# Level_Shifter.net
KiCad netlist of a schematic drawn in Altium Designer
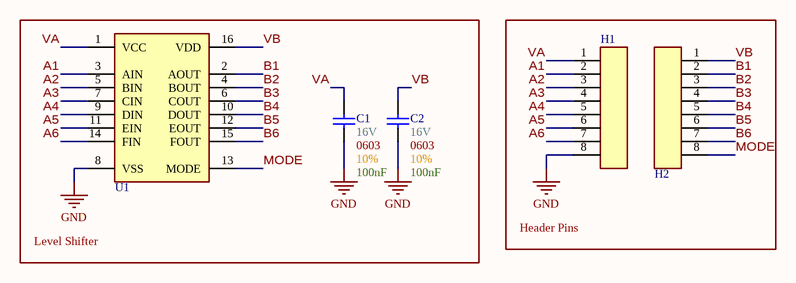
[diagram p0: Level Shifter.SchDoc]

(export (version "E")
  (design (tool "Eeschema 10.0.6"))
  (components
    (comp (ref "C1")
      (value "[Cap] 0603 0.1uF 10% 16V")
      (footprint "[Cap] SMD 0603")
      (description "CC0603KRX7R7BB104")
      (fields
        (field (name "MAX VOLTAGE") "16V")
        (field (name "SIZE PACKAGE") "0603")
        (field (name "TOLERANCE") "10%")
        (field (name "CAPACITANCE") "100nF")
      )
      (libsource (lib "Capacitors") (part "[Cap] 0603 0.1uF 10% 16V"))
    )
    (comp (ref "C2")
      (value "[Cap] 0603 0.1uF 10% 16V")
      (footprint "[Cap] SMD 0603")
      (description "CC0603KRX7R7BB104")
      (fields
        (field (name "MAX VOLTAGE") "16V")
        (field (name "SIZE PACKAGE") "0603")
        (field (name "TOLERANCE") "10%")
        (field (name "CAPACITANCE") "100nF")
      )
      (libsource (lib "Capacitors") (part "[Cap] 0603 0.1uF 10% 16V"))
    )
    (comp (ref "H1")
      (value "1x8 Header")
      (footprint "[Header] 1x8 Male")
      (description "2.54mm pitch")
      (libsource (lib "") (part "[Header] 1x8 Male_1"))
    )
    (comp (ref "H2")
      (value "1x8 Header")
      (footprint "[Header] 1x8 Male")
      (description "2.54mm pitch")
      (libsource (lib "Connectors") (part "[Header] 1x8 Male"))
    )
    (comp (ref "U1")
      (value "[Level Shifter] 3-18V Unidirectional")
      (footprint "[Level Shifter] 3-18V Unidirectional")
      (description "MC14504BDTR2G")
      (libsource (lib "ICs") (part "[Level Shifter] 3-18V Unidirectional"))
    )
  )
  (nets
    (net (code "1") (name "/A1") (class "Default")
      (node (ref "H1") (pin "2") (pinfunction "2_2") (pintype "passive"))
      (node (ref "U1") (pin "3") (pinfunction "AIN_3") (pintype "passive"))
    )
    (net (code "2") (name "/A2") (class "Default")
      (node (ref "H1") (pin "3") (pinfunction "3_3") (pintype "passive"))
      (node (ref "U1") (pin "5") (pinfunction "BIN_5") (pintype "passive"))
    )
    (net (code "3") (name "/A3") (class "Default")
      (node (ref "H1") (pin "4") (pinfunction "4_4") (pintype "passive"))
      (node (ref "U1") (pin "7") (pinfunction "CIN_7") (pintype "passive"))
    )
    (net (code "4") (name "/A4") (class "Default")
      (node (ref "H1") (pin "5") (pinfunction "5_5") (pintype "passive"))
      (node (ref "U1") (pin "9") (pinfunction "DIN_9") (pintype "passive"))
    )
    (net (code "5") (name "/A5") (class "Default")
      (node (ref "H1") (pin "6") (pinfunction "6_6") (pintype "passive"))
      (node (ref "U1") (pin "11") (pinfunction "EIN_11") (pintype "passive"))
    )
    (net (code "6") (name "/A6") (class "Default")
      (node (ref "H1") (pin "7") (pinfunction "7_7") (pintype "passive"))
      (node (ref "U1") (pin "14") (pinfunction "FIN_14") (pintype "passive"))
    )
    (net (code "7") (name "/B1") (class "Default")
      (node (ref "H2") (pin "2") (pinfunction "2_2") (pintype "passive"))
      (node (ref "U1") (pin "2") (pinfunction "AOUT_2") (pintype "passive"))
    )
    (net (code "8") (name "/B2") (class "Default")
      (node (ref "H2") (pin "3") (pinfunction "3_3") (pintype "passive"))
      (node (ref "U1") (pin "4") (pinfunction "BOUT_4") (pintype "passive"))
    )
    (net (code "9") (name "/B3") (class "Default")
      (node (ref "H2") (pin "4") (pinfunction "4_4") (pintype "passive"))
      (node (ref "U1") (pin "6") (pinfunction "COUT_6") (pintype "passive"))
    )
    (net (code "10") (name "/B4") (class "Default")
      (node (ref "H2") (pin "5") (pinfunction "5_5") (pintype "passive"))
      (node (ref "U1") (pin "10") (pinfunction "DOUT_10") (pintype "passive"))
    )
    (net (code "11") (name "/B5") (class "Default")
      (node (ref "H2") (pin "6") (pinfunction "6_6") (pintype "passive"))
      (node (ref "U1") (pin "12") (pinfunction "EOUT_12") (pintype "passive"))
    )
    (net (code "12") (name "/B6") (class "Default")
      (node (ref "H2") (pin "7") (pinfunction "7_7") (pintype "passive"))
      (node (ref "U1") (pin "15") (pinfunction "FOUT_15") (pintype "passive"))
    )
    (net (code "13") (name "/MODE") (class "Default")
      (node (ref "H2") (pin "8") (pinfunction "8_8") (pintype "passive"))
      (node (ref "U1") (pin "13") (pinfunction "MODE_13") (pintype "passive"))
    )
    (net (code "14") (name "/VA") (class "Default")
      (node (ref "C1") (pin "2") (pinfunction "2_2") (pintype "passive"))
      (node (ref "H1") (pin "1") (pinfunction "1_1") (pintype "passive"))
      (node (ref "U1") (pin "1") (pinfunction "VCC_1") (pintype "passive"))
    )
    (net (code "15") (name "/VB") (class "Default")
      (node (ref "C2") (pin "2") (pinfunction "2_2") (pintype "passive"))
      (node (ref "H2") (pin "1") (pinfunction "1_1") (pintype "passive"))
      (node (ref "U1") (pin "16") (pinfunction "VDD_16") (pintype "passive"))
    )
    (net (code "16") (name "GND") (class "Default")
      (node (ref "C1") (pin "1") (pinfunction "1_1") (pintype "passive"))
      (node (ref "C2") (pin "1") (pinfunction "1_1") (pintype "passive"))
      (node (ref "H1") (pin "8") (pinfunction "8_8") (pintype "passive"))
      (node (ref "U1") (pin "8") (pinfunction "VSS_8") (pintype "passive"))
    )
  )
)
